# Un_Battery_V3_0.net
KiCad netlist of a schematic drawn in EAGLE
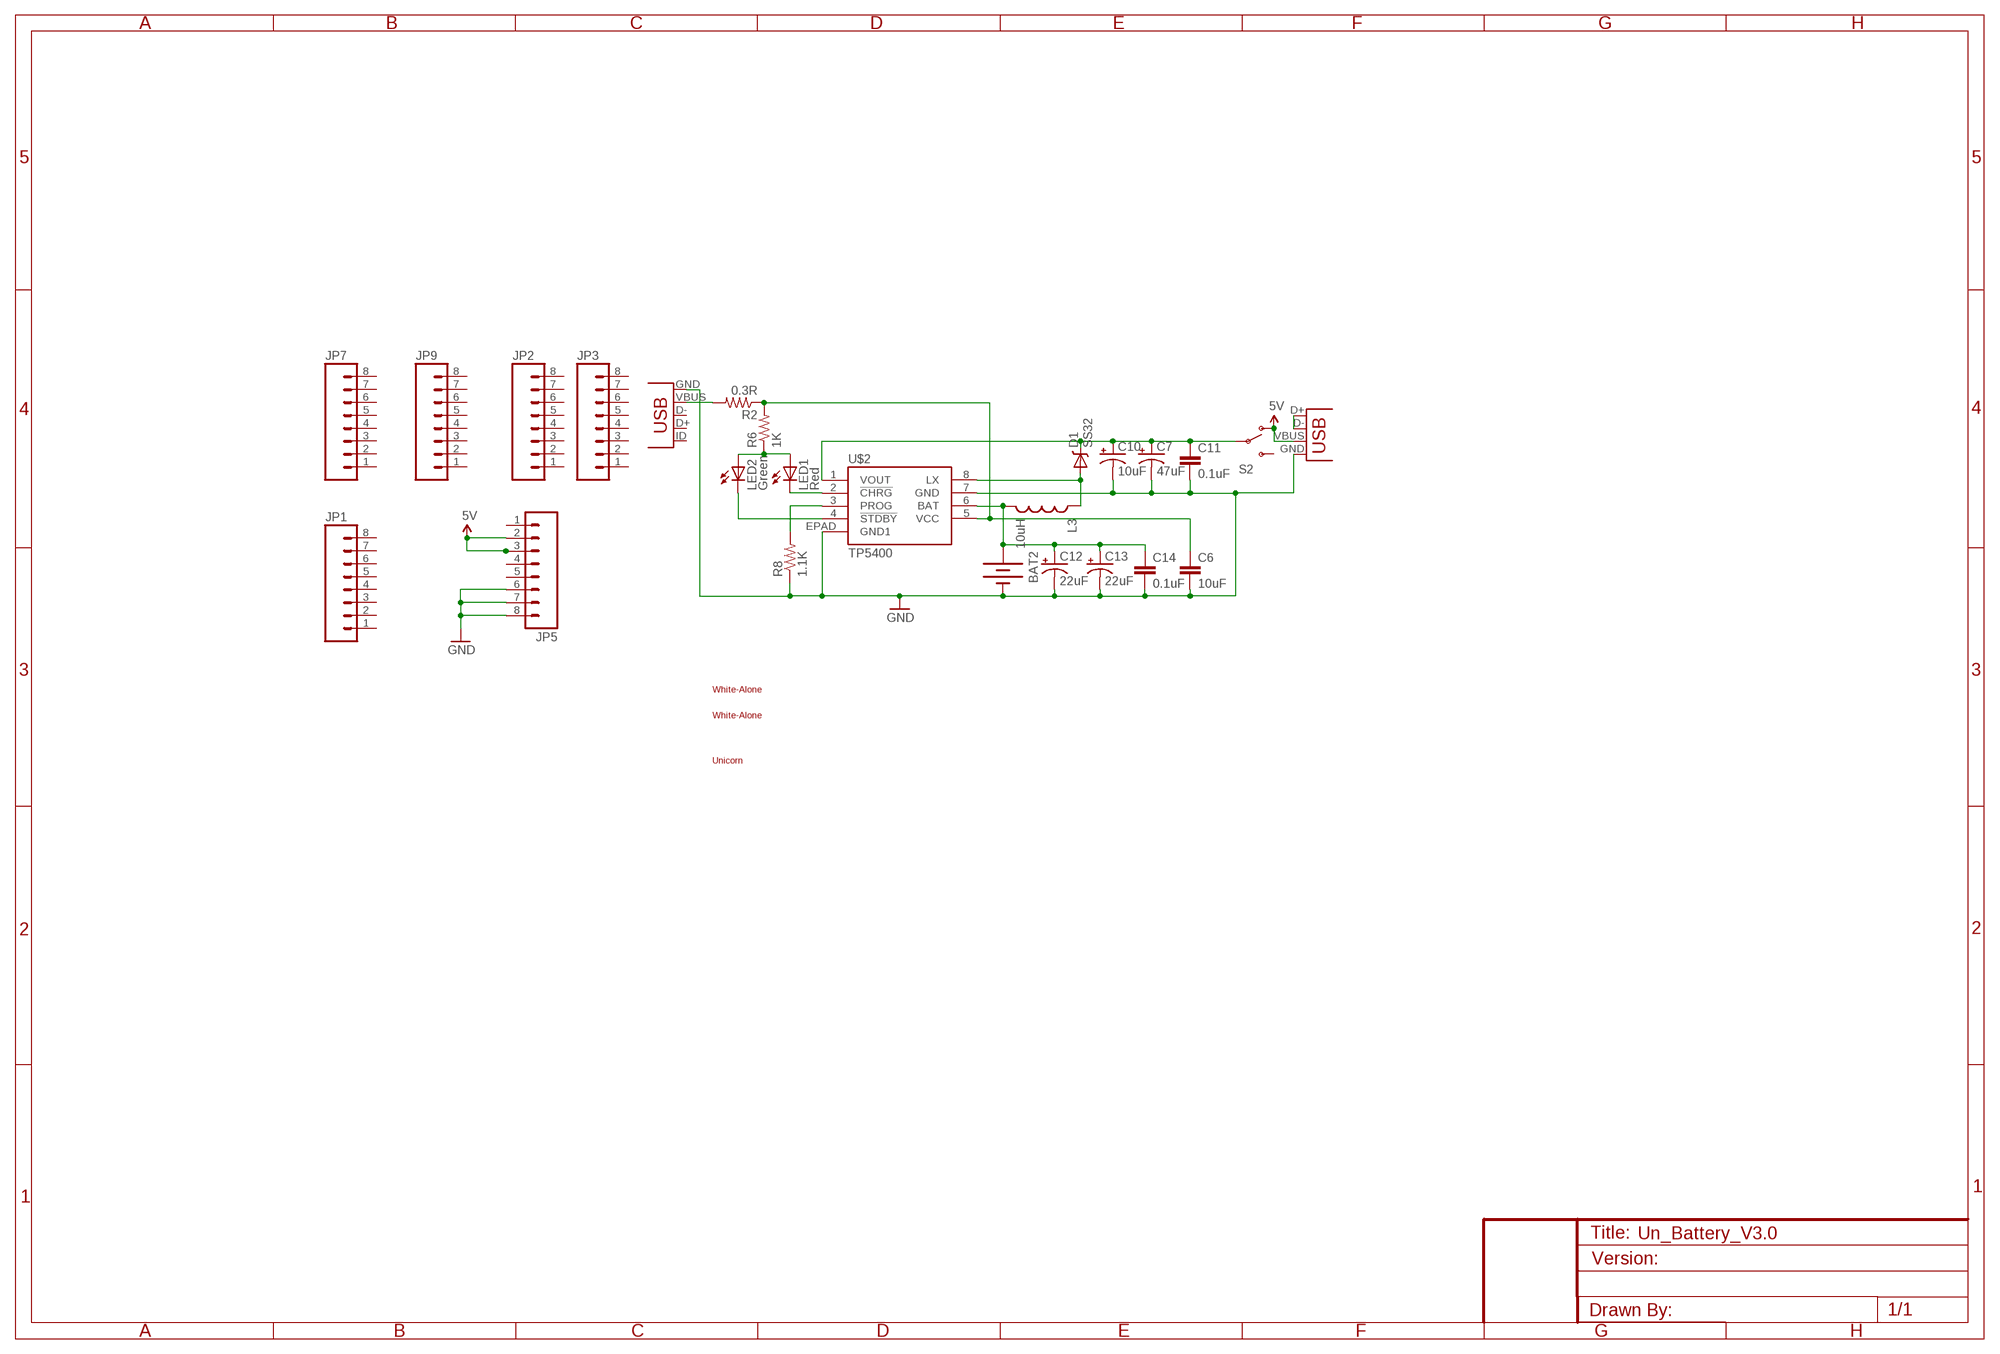
[diagram p0: schematic, sheet 1]

(export (version "E")
  (design (tool "Eeschema 10.0.6"))
  (components
    (comp (ref "BAT2")
      (value "BATTERYLIPO")
      (footprint "eagle-import:BATTERY-LIPO")
      (libsource (lib "eagle-import") (part "BATTERYLIPO"))
    )
    (comp (ref "C6")
      (value "10uF")
      (footprint "eagle-import:1206")
      (libsource (lib "eagle-import") (part "CAP1206"))
    )
    (comp (ref "C7")
      (value "47uF")
      (footprint "eagle-import:PANASONIC_D")
      (libsource (lib "eagle-import") (part "CAP_POLD"))
    )
    (comp (ref "C10")
      (value "10uF")
      (footprint "eagle-import:EIA3216")
      (libsource (lib "eagle-import") (part "CAP_POL1206"))
    )
    (comp (ref "C11")
      (value "0.1uF")
      (footprint "eagle-import:1206")
      (libsource (lib "eagle-import") (part "CAP1206"))
    )
    (comp (ref "C12")
      (value "22uF")
      (footprint "eagle-import:EIA3216")
      (libsource (lib "eagle-import") (part "CAP_POL1206"))
    )
    (comp (ref "C13")
      (value "22uF")
      (footprint "eagle-import:EIA3216")
      (libsource (lib "eagle-import") (part "CAP_POL1206"))
    )
    (comp (ref "C14")
      (value "0.1uF")
      (footprint "eagle-import:1206")
      (libsource (lib "eagle-import") (part "CAP1206"))
    )
    (comp (ref "D1")
      (value "SS32")
      (footprint "eagle-import:SMA-DIODE")
      (libsource (lib "eagle-import") (part "DIODE-SCHOTTKY_"))
    )
    (comp (ref "JP1")
      (value "M081X08")
      (footprint "eagle-import:1X08")
      (libsource (lib "eagle-import") (part "M081X08"))
    )
    (comp (ref "JP2")
      (value "M081X08")
      (footprint "eagle-import:1X08")
      (libsource (lib "eagle-import") (part "M081X08"))
    )
    (comp (ref "JP3")
      (value "M081X08")
      (footprint "eagle-import:1X08")
      (libsource (lib "eagle-import") (part "M081X08"))
    )
    (comp (ref "JP5")
      (value "M081X08")
      (footprint "eagle-import:1X08")
      (libsource (lib "eagle-import") (part "M081X08"))
    )
    (comp (ref "JP7")
      (value "M081X08")
      (footprint "eagle-import:1X08")
      (libsource (lib "eagle-import") (part "M081X08"))
    )
    (comp (ref "JP9")
      (value "M081X08")
      (footprint "eagle-import:1X08")
      (libsource (lib "eagle-import") (part "M081X08"))
    )
    (comp (ref "L3")
      (value "10uH")
      (footprint "eagle-import:CR75")
      (libsource (lib "eagle-import") (part "INDUCTORCR75"))
    )
    (comp (ref "LED1")
      (value "Red")
      (footprint "eagle-import:LED-0805")
      (libsource (lib "eagle-import") (part "LED0805"))
    )
    (comp (ref "LED2")
      (value "Green")
      (footprint "eagle-import:LED-0805")
      (libsource (lib "eagle-import") (part "LED0805"))
    )
    (comp (ref "R2")
      (value "0.3R")
      (footprint "eagle-import:1206")
      (libsource (lib "eagle-import") (part "RESISTOR1206"))
    )
    (comp (ref "R6")
      (value "1K")
      (footprint "eagle-import:0805")
      (libsource (lib "eagle-import") (part "RESISTOR0805-RES"))
    )
    (comp (ref "R8")
      (value "1.1K")
      (footprint "eagle-import:0805")
      (libsource (lib "eagle-import") (part "RESISTOR0805-RES"))
    )
    (comp (ref "S2")
      (value "SWITCH-SPST")
      (footprint "eagle-import:SWITCH-SPDT2")
      (libsource (lib "eagle-import") (part "SWITCH-SPST"))
    )
    (comp (ref "U$2")
      (value "TP5400")
      (footprint "eagle-import:SO08-EPAD")
      (libsource (lib "eagle-import") (part "TP5400"))
    )
    (comp (ref "U$4")
      (value "WHITE-ALONE_2")
      (footprint "eagle-import:WHITE-ALONE_2")
      (libsource (lib "eagle-import") (part "WHITE-ALONE_2"))
    )
    (comp (ref "U$5")
      (value "WHITE-ALONE_2")
      (footprint "eagle-import:WHITE-ALONE_2")
      (libsource (lib "eagle-import") (part "WHITE-ALONE_2"))
    )
    (comp (ref "U$6")
      (value "USB_5-SMD")
      (footprint "eagle-import:USB-MINIB")
      (libsource (lib "eagle-import") (part "USB_5-SMD"))
    )
    (comp (ref "U$7")
      (value "UNICORN_2")
      (footprint "eagle-import:UNICORN_2")
      (libsource (lib "eagle-import") (part "UNICORN_2"))
    )
    (comp (ref "X2")
      (value "USB-A-S")
      (footprint "eagle-import:USB-A-S")
      (libsource (lib "eagle-import") (part "USB-A-S"))
    )
  )
  (nets
    (net (code "1") (name "5V") (class "Default")
      (node (ref "JP5") (pin "2") (pinfunction "2_2") (pintype "passive"))
      (node (ref "JP5") (pin "3") (pinfunction "3_3") (pintype "passive"))
      (node (ref "S2") (pin "1") (pinfunction "O_1") (pintype "passive"))
      (node (ref "X2") (pin "VBUS") (pinfunction "VBUS_VBUS") (pintype "bidirectional"))
    )
    (net (code "2") (name "GND") (class "Default")
      (node (ref "BAT2") (pin "-") (pinfunction "-_-") (pintype "power_in"))
      (node (ref "C10") (pin "C") (pinfunction "-_C") (pintype "passive"))
      (node (ref "C11") (pin "2") (pinfunction "2_2") (pintype "passive"))
      (node (ref "C12") (pin "C") (pinfunction "-_C") (pintype "passive"))
      (node (ref "C13") (pin "C") (pinfunction "-_C") (pintype "passive"))
      (node (ref "C14") (pin "2") (pinfunction "2_2") (pintype "passive"))
      (node (ref "C6") (pin "2") (pinfunction "2_2") (pintype "passive"))
      (node (ref "C7") (pin "-") (pinfunction "-_-") (pintype "passive"))
      (node (ref "JP5") (pin "6") (pinfunction "6_6") (pintype "passive"))
      (node (ref "JP5") (pin "7") (pinfunction "7_7") (pintype "passive"))
      (node (ref "JP5") (pin "8") (pinfunction "8_8") (pintype "passive"))
      (node (ref "R8") (pin "1") (pinfunction "1_1") (pintype "passive"))
      (node (ref "U$2") (pin "7") (pinfunction "GND_7") (pintype "bidirectional"))
      (node (ref "U$2") (pin "EPAD") (pinfunction "GND1_EPAD") (pintype "power_in"))
      (node (ref "U$6") (pin "GND") (pinfunction "GND_GND") (pintype "bidirectional"))
      (node (ref "X2") (pin "GND") (pinfunction "GND_GND") (pintype "bidirectional"))
    )
    (net (code "3") (name "Net-(C10-+)") (class "Default")
      (node (ref "C10") (pin "A") (pinfunction "+_A") (pintype "passive"))
      (node (ref "C11") (pin "1") (pinfunction "1_1") (pintype "passive"))
      (node (ref "C7") (pin "+") (pinfunction "+_+") (pintype "passive"))
      (node (ref "D1") (pin "C") (pinfunction "C_C") (pintype "passive"))
      (node (ref "S2") (pin "2") (pinfunction "P_2") (pintype "passive"))
      (node (ref "U$2") (pin "1") (pinfunction "VOUT_1") (pintype "bidirectional"))
    )
    (net (code "4") (name "Net-(C12-+)") (class "Default")
      (node (ref "BAT2") (pin "+") (pinfunction "+_+") (pintype "power_in"))
      (node (ref "C12") (pin "A") (pinfunction "+_A") (pintype "passive"))
      (node (ref "C13") (pin "A") (pinfunction "+_A") (pintype "passive"))
      (node (ref "C14") (pin "1") (pinfunction "1_1") (pintype "passive"))
      (node (ref "L3") (pin "P$2") (pinfunction "2_P$2") (pintype "passive"))
      (node (ref "U$2") (pin "6") (pinfunction "BAT_6") (pintype "bidirectional"))
    )
    (net (code "5") (name "Net-(L3-1)") (class "Default")
      (node (ref "D1") (pin "A") (pinfunction "A_A") (pintype "passive"))
      (node (ref "L3") (pin "P$1") (pinfunction "1_P$1") (pintype "passive"))
      (node (ref "U$2") (pin "8") (pinfunction "LX_8") (pintype "power_in"))
    )
    (net (code "6") (name "Net-(LED1-A)") (class "Default")
      (node (ref "LED1") (pin "1") (pinfunction "A_1") (pintype "passive"))
      (node (ref "LED2") (pin "1") (pinfunction "A_1") (pintype "passive"))
      (node (ref "R6") (pin "1") (pinfunction "1_1") (pintype "passive"))
    )
    (net (code "7") (name "Net-(LED1-C)") (class "Default")
      (node (ref "LED1") (pin "2") (pinfunction "C_2") (pintype "passive"))
      (node (ref "U$2") (pin "2") (pinfunction "~{CHRG}_2") (pintype "bidirectional"))
    )
    (net (code "8") (name "Net-(LED2-C)") (class "Default")
      (node (ref "LED2") (pin "2") (pinfunction "C_2") (pintype "passive"))
      (node (ref "U$2") (pin "4") (pinfunction "~{STDBY}_4") (pintype "power_in"))
    )
    (net (code "9") (name "Net-(R2-Pad2)") (class "Default")
      (node (ref "R2") (pin "2") (pinfunction "2_2") (pintype "passive"))
      (node (ref "U$6") (pin "VBUS") (pinfunction "VBUS_VBUS") (pintype "bidirectional"))
    )
    (net (code "10") (name "Net-(U$2-PROG)") (class "Default")
      (node (ref "R8") (pin "2") (pinfunction "2_2") (pintype "passive"))
      (node (ref "U$2") (pin "3") (pinfunction "PROG_3") (pintype "bidirectional"))
    )
    (net (code "11") (name "Net-(U$2-VCC)") (class "Default")
      (node (ref "C6") (pin "1") (pinfunction "1_1") (pintype "passive"))
      (node (ref "R2") (pin "1") (pinfunction "1_1") (pintype "passive"))
      (node (ref "R6") (pin "2") (pinfunction "2_2") (pintype "passive"))
      (node (ref "U$2") (pin "5") (pinfunction "VCC_5") (pintype "bidirectional"))
    )
    (net (code "12") (name "Net-(X2-PadD+)") (class "Default")
      (node (ref "X2") (pin "D+") (pinfunction "D+_D+") (pintype "bidirectional"))
      (node (ref "X2") (pin "D-") (pinfunction "D-_D-") (pintype "bidirectional"))
    )
    (net (code "13") (name "unconnected-(JP1-Pad1)") (class "Default")
      (node (ref "JP1") (pin "1") (pinfunction "1_1") (pintype "passive"))
    )
    (net (code "14") (name "unconnected-(JP1-Pad2)") (class "Default")
      (node (ref "JP1") (pin "2") (pinfunction "2_2") (pintype "passive"))
    )
    (net (code "15") (name "unconnected-(JP1-Pad3)") (class "Default")
      (node (ref "JP1") (pin "3") (pinfunction "3_3") (pintype "passive"))
    )
    (net (code "16") (name "unconnected-(JP1-Pad4)") (class "Default")
      (node (ref "JP1") (pin "4") (pinfunction "4_4") (pintype "passive"))
    )
    (net (code "17") (name "unconnected-(JP1-Pad5)") (class "Default")
      (node (ref "JP1") (pin "5") (pinfunction "5_5") (pintype "passive"))
    )
    (net (code "18") (name "unconnected-(JP1-Pad6)") (class "Default")
      (node (ref "JP1") (pin "6") (pinfunction "6_6") (pintype "passive"))
    )
    (net (code "19") (name "unconnected-(JP1-Pad7)") (class "Default")
      (node (ref "JP1") (pin "7") (pinfunction "7_7") (pintype "passive"))
    )
    (net (code "20") (name "unconnected-(JP1-Pad8)") (class "Default")
      (node (ref "JP1") (pin "8") (pinfunction "8_8") (pintype "passive"))
    )
    (net (code "21") (name "unconnected-(JP2-Pad1)") (class "Default")
      (node (ref "JP2") (pin "1") (pinfunction "1_1") (pintype "passive"))
    )
    (net (code "22") (name "unconnected-(JP2-Pad2)") (class "Default")
      (node (ref "JP2") (pin "2") (pinfunction "2_2") (pintype "passive"))
    )
    (net (code "23") (name "unconnected-(JP2-Pad3)") (class "Default")
      (node (ref "JP2") (pin "3") (pinfunction "3_3") (pintype "passive"))
    )
    (net (code "24") (name "unconnected-(JP2-Pad4)") (class "Default")
      (node (ref "JP2") (pin "4") (pinfunction "4_4") (pintype "passive"))
    )
    (net (code "25") (name "unconnected-(JP2-Pad5)") (class "Default")
      (node (ref "JP2") (pin "5") (pinfunction "5_5") (pintype "passive"))
    )
    (net (code "26") (name "unconnected-(JP2-Pad6)") (class "Default")
      (node (ref "JP2") (pin "6") (pinfunction "6_6") (pintype "passive"))
    )
    (net (code "27") (name "unconnected-(JP2-Pad7)") (class "Default")
      (node (ref "JP2") (pin "7") (pinfunction "7_7") (pintype "passive"))
    )
    (net (code "28") (name "unconnected-(JP2-Pad8)") (class "Default")
      (node (ref "JP2") (pin "8") (pinfunction "8_8") (pintype "passive"))
    )
    (net (code "29") (name "unconnected-(JP3-Pad1)") (class "Default")
      (node (ref "JP3") (pin "1") (pinfunction "1_1") (pintype "passive"))
    )
    (net (code "30") (name "unconnected-(JP3-Pad2)") (class "Default")
      (node (ref "JP3") (pin "2") (pinfunction "2_2") (pintype "passive"))
    )
    (net (code "31") (name "unconnected-(JP3-Pad3)") (class "Default")
      (node (ref "JP3") (pin "3") (pinfunction "3_3") (pintype "passive"))
    )
    (net (code "32") (name "unconnected-(JP3-Pad4)") (class "Default")
      (node (ref "JP3") (pin "4") (pinfunction "4_4") (pintype "passive"))
    )
    (net (code "33") (name "unconnected-(JP3-Pad5)") (class "Default")
      (node (ref "JP3") (pin "5") (pinfunction "5_5") (pintype "passive"))
    )
    (net (code "34") (name "unconnected-(JP3-Pad6)") (class "Default")
      (node (ref "JP3") (pin "6") (pinfunction "6_6") (pintype "passive"))
    )
    (net (code "35") (name "unconnected-(JP3-Pad7)") (class "Default")
      (node (ref "JP3") (pin "7") (pinfunction "7_7") (pintype "passive"))
    )
    (net (code "36") (name "unconnected-(JP3-Pad8)") (class "Default")
      (node (ref "JP3") (pin "8") (pinfunction "8_8") (pintype "passive"))
    )
    (net (code "37") (name "unconnected-(JP5-Pad1)") (class "Default")
      (node (ref "JP5") (pin "1") (pinfunction "1_1") (pintype "passive"))
    )
    (net (code "38") (name "unconnected-(JP5-Pad4)") (class "Default")
      (node (ref "JP5") (pin "4") (pinfunction "4_4") (pintype "passive"))
    )
    (net (code "39") (name "unconnected-(JP5-Pad5)") (class "Default")
      (node (ref "JP5") (pin "5") (pinfunction "5_5") (pintype "passive"))
    )
    (net (code "40") (name "unconnected-(JP7-Pad1)") (class "Default")
      (node (ref "JP7") (pin "1") (pinfunction "1_1") (pintype "passive"))
    )
    (net (code "41") (name "unconnected-(JP7-Pad2)") (class "Default")
      (node (ref "JP7") (pin "2") (pinfunction "2_2") (pintype "passive"))
    )
    (net (code "42") (name "unconnected-(JP7-Pad3)") (class "Default")
      (node (ref "JP7") (pin "3") (pinfunction "3_3") (pintype "passive"))
    )
    (net (code "43") (name "unconnected-(JP7-Pad4)") (class "Default")
      (node (ref "JP7") (pin "4") (pinfunction "4_4") (pintype "passive"))
    )
    (net (code "44") (name "unconnected-(JP7-Pad5)") (class "Default")
      (node (ref "JP7") (pin "5") (pinfunction "5_5") (pintype "passive"))
    )
    (net (code "45") (name "unconnected-(JP7-Pad6)") (class "Default")
      (node (ref "JP7") (pin "6") (pinfunction "6_6") (pintype "passive"))
    )
    (net (code "46") (name "unconnected-(JP7-Pad7)") (class "Default")
      (node (ref "JP7") (pin "7") (pinfunction "7_7") (pintype "passive"))
    )
    (net (code "47") (name "unconnected-(JP7-Pad8)") (class "Default")
      (node (ref "JP7") (pin "8") (pinfunction "8_8") (pintype "passive"))
    )
    (net (code "48") (name "unconnected-(JP9-Pad1)") (class "Default")
      (node (ref "JP9") (pin "1") (pinfunction "1_1") (pintype "passive"))
    )
    (net (code "49") (name "unconnected-(JP9-Pad2)") (class "Default")
      (node (ref "JP9") (pin "2") (pinfunction "2_2") (pintype "passive"))
    )
    (net (code "50") (name "unconnected-(JP9-Pad3)") (class "Default")
      (node (ref "JP9") (pin "3") (pinfunction "3_3") (pintype "passive"))
    )
    (net (code "51") (name "unconnected-(JP9-Pad4)") (class "Default")
      (node (ref "JP9") (pin "4") (pinfunction "4_4") (pintype "passive"))
    )
    (net (code "52") (name "unconnected-(JP9-Pad5)") (class "Default")
      (node (ref "JP9") (pin "5") (pinfunction "5_5") (pintype "passive"))
    )
    (net (code "53") (name "unconnected-(JP9-Pad6)") (class "Default")
      (node (ref "JP9") (pin "6") (pinfunction "6_6") (pintype "passive"))
    )
    (net (code "54") (name "unconnected-(JP9-Pad7)") (class "Default")
      (node (ref "JP9") (pin "7") (pinfunction "7_7") (pintype "passive"))
    )
    (net (code "55") (name "unconnected-(JP9-Pad8)") (class "Default")
      (node (ref "JP9") (pin "8") (pinfunction "8_8") (pintype "passive"))
    )
    (net (code "56") (name "unconnected-(S2-S-Pad3)") (class "Default")
      (node (ref "S2") (pin "3") (pinfunction "S_3") (pintype "passive"))
    )
    (net (code "57") (name "unconnected-(U$6-PadD+)") (class "Default")
      (node (ref "U$6") (pin "D+") (pinfunction "D+_D+") (pintype "bidirectional"))
    )
    (net (code "58") (name "unconnected-(U$6-PadD-)") (class "Default")
      (node (ref "U$6") (pin "D-") (pinfunction "D-_D-") (pintype "bidirectional"))
    )
    (net (code "59") (name "unconnected-(U$6-USBID-PadID)") (class "Default")
      (node (ref "U$6") (pin "ID") (pinfunction "USBID_ID") (pintype "bidirectional"))
    )
  )
)
